# Main.net
KiCad netlist of a schematic drawn in Altium Designer
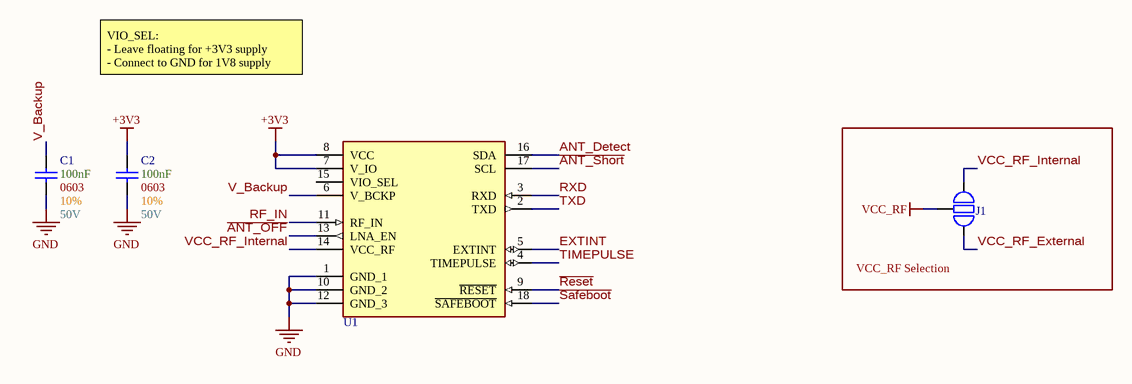
[diagram p0: Main.SchDoc]

(export (version "E")
  (design (tool "Eeschema 10.0.6"))
  (components
    (comp (ref "C1")
      (value "[Cap] 0603 0.1uF 10% 50V")
      (footprint "[Cap] SMD 0603")
      (description "CL10B104KB8NNNC")
      (fields
        (field (name "MAX VOLTAGE") "50V")
        (field (name "SIZE PACKAGE") "0603")
        (field (name "TOLERANCE") "10%")
        (field (name "CAPACITANCE") "100nF")
      )
      (libsource (lib "Capacitors") (part "[Cap] 0603 0.1uF 10% 50V"))
    )
    (comp (ref "C2")
      (value "[Cap] 0603 0.1uF 10% 50V")
      (footprint "[Cap] SMD 0603")
      (description "CL10B104KB8NNNC")
      (fields
        (field (name "MAX VOLTAGE") "50V")
        (field (name "SIZE PACKAGE") "0603")
        (field (name "TOLERANCE") "10%")
        (field (name "CAPACITANCE") "100nF")
      )
      (libsource (lib "Capacitors") (part "[Cap] 0603 0.1uF 10% 50V"))
    )
    (comp (ref "J1")
      (value "[Jumper] Thru-Hole 3pin")
      (footprint "[Jumper] Thru-Hole 3pin")
      (libsource (lib "Misc Components") (part "[Jumper] Thru-Hole 3pin"))
    )
    (comp (ref "U1")
      (value "Dual-Band GNSS Module")
      (footprint "[GNSS] MAX-F10S-00B")
      (description "MAX-F10S-00B")
      (libsource (lib "ICs") (part "[GNSS] MAX-F10S-00B"))
    )
  )
  (nets
    (net (code "1") (name "+3V3") (class "Default")
      (node (ref "C2") (pin "2") (pinfunction "2_2") (pintype "passive"))
      (node (ref "U1") (pin "7") (pinfunction "V_IO_7") (pintype "power_in"))
      (node (ref "U1") (pin "8") (pinfunction "VCC_8") (pintype "power_in"))
    )
    (net (code "2") (name "/ANT_Detect") (class "Default")
      (node (ref "U1") (pin "16") (pinfunction "SDA_16") (pintype "passive"))
    )
    (net (code "3") (name "/ANT_OFF") (class "Default")
      (node (ref "U1") (pin "13") (pinfunction "LNA_EN_13") (pintype "output"))
    )
    (net (code "4") (name "/ANT_Short") (class "Default")
      (node (ref "U1") (pin "17") (pinfunction "SCL_17") (pintype "passive"))
    )
    (net (code "5") (name "/EXTINT") (class "Default")
      (node (ref "U1") (pin "5") (pinfunction "EXTINT_5") (pintype "bidirectional"))
    )
    (net (code "6") (name "/RF_IN") (class "Default")
      (node (ref "U1") (pin "11") (pinfunction "RF_IN_11") (pintype "input"))
    )
    (net (code "7") (name "/RXD") (class "Default")
      (node (ref "U1") (pin "3") (pinfunction "RXD_3") (pintype "input"))
    )
    (net (code "8") (name "/Reset") (class "Default")
      (node (ref "U1") (pin "9") (pinfunction "RESET_9") (pintype "input"))
    )
    (net (code "9") (name "/Safeboot") (class "Default")
      (node (ref "U1") (pin "18") (pinfunction "SAFEBOOT_18") (pintype "input"))
    )
    (net (code "10") (name "/TIMEPULSE") (class "Default")
      (node (ref "U1") (pin "4") (pinfunction "TIMEPULSE_4") (pintype "bidirectional"))
    )
    (net (code "11") (name "/TXD") (class "Default")
      (node (ref "U1") (pin "2") (pinfunction "TXD_2") (pintype "output"))
    )
    (net (code "12") (name "/VCC_RF_External") (class "Default")
      (node (ref "J1") (pin "3") (pintype "passive"))
    )
    (net (code "13") (name "/VCC_RF_Internal") (class "Default")
      (node (ref "J1") (pin "1") (pintype "passive"))
      (node (ref "U1") (pin "14") (pinfunction "VCC_RF_14") (pintype "power_in"))
    )
    (net (code "14") (name "/V_Backup") (class "Default")
      (node (ref "C1") (pin "2") (pinfunction "2_2") (pintype "passive"))
      (node (ref "U1") (pin "6") (pinfunction "V_BCKP_6") (pintype "power_in"))
    )
    (net (code "15") (name "GND") (class "Default")
      (node (ref "C1") (pin "1") (pinfunction "1_1") (pintype "passive"))
      (node (ref "C2") (pin "1") (pinfunction "1_1") (pintype "passive"))
      (node (ref "U1") (pin "1") (pinfunction "GND_1_1") (pintype "power_in"))
      (node (ref "U1") (pin "10") (pinfunction "GND_2_10") (pintype "power_in"))
      (node (ref "U1") (pin "12") (pinfunction "GND_3_12") (pintype "power_in"))
    )
    (net (code "16") (name "VCC_RF") (class "Default")
      (node (ref "J1") (pin "2") (pinfunction "Common_2") (pintype "power_in"))
    )
    (net (code "17") (name "unconnected-(U1-VIO_SEL-Pad15)") (class "Default")
      (node (ref "U1") (pin "15") (pinfunction "VIO_SEL_15") (pintype "power_in"))
    )
  )
)
